# SquareSprite.net
KiCad netlist of a schematic drawn in EAGLE
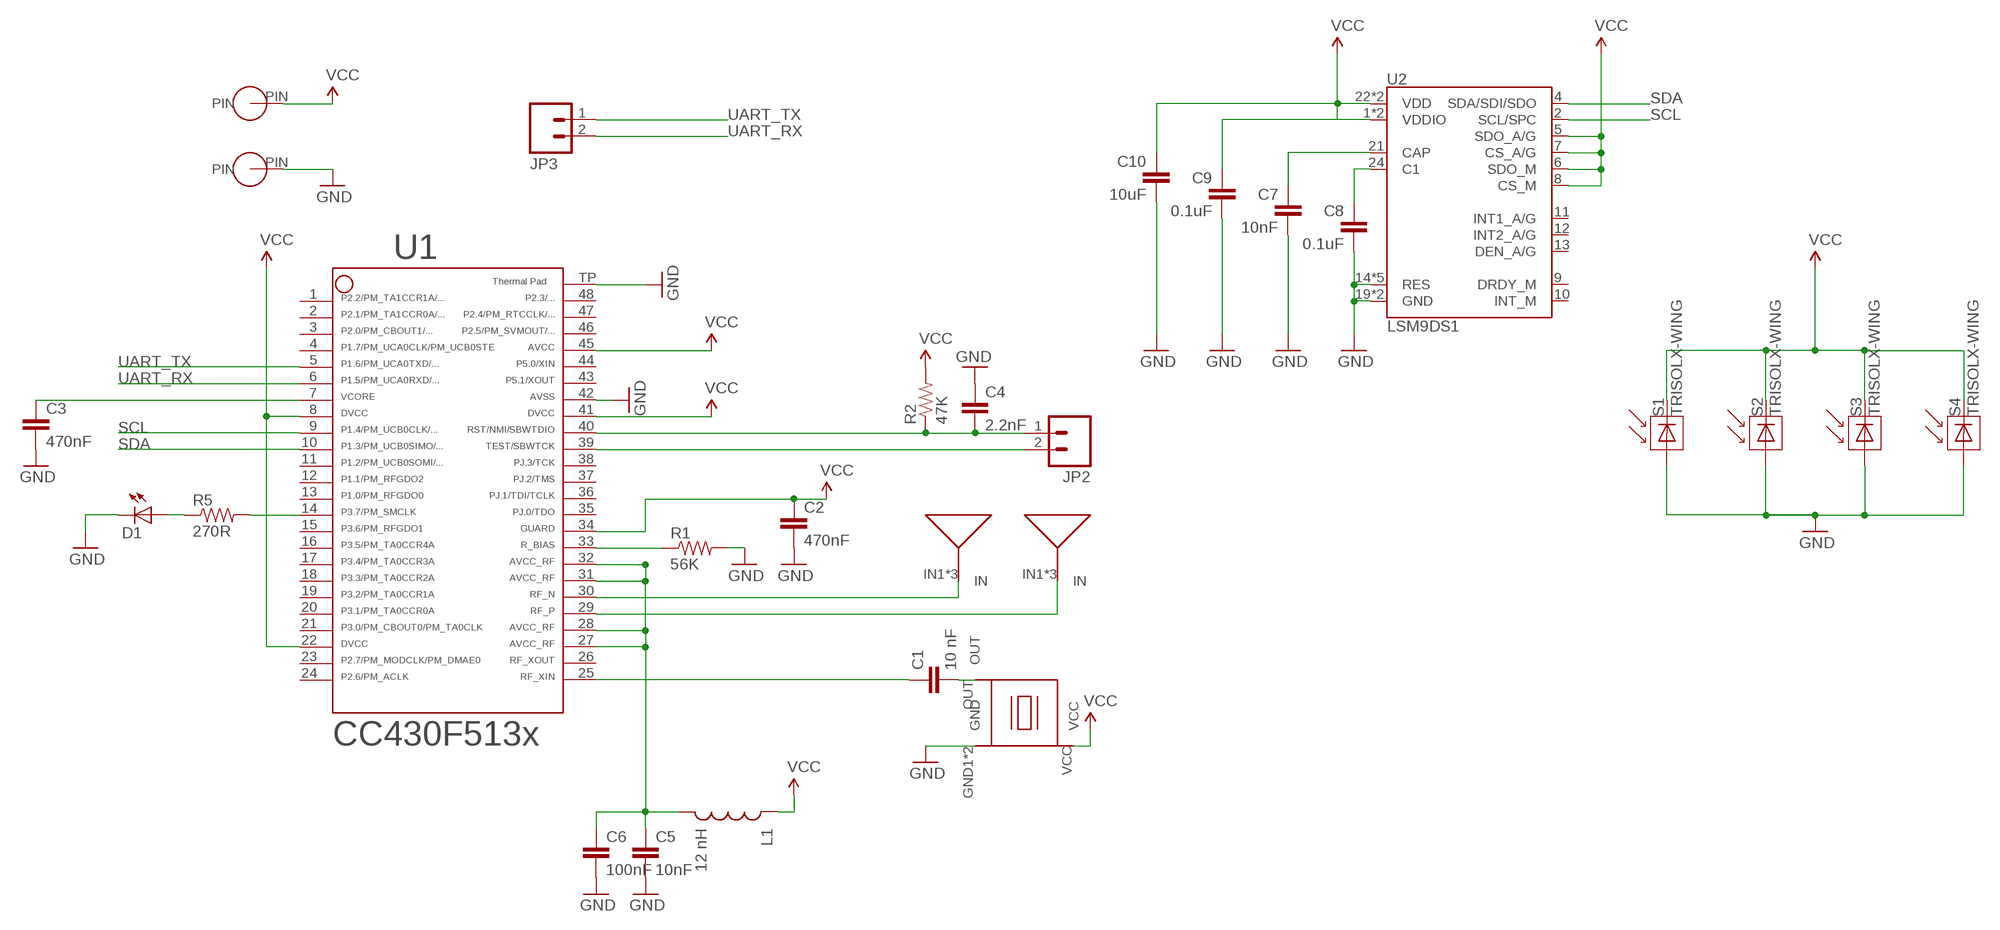
[diagram p0: schematic, sheet 1]

(export (version "E")
  (design (tool "Eeschema 10.0.6"))
  (components
    (comp (ref "ANT-N")
      (value "ANTENNA")
      (footprint "eagle-import:ANTENNA")
      (libsource (lib "eagle-import") (part "ANTENNA"))
    )
    (comp (ref "ANT-P")
      (value "ANTENNA")
      (footprint "eagle-import:ANTENNA")
      (libsource (lib "eagle-import") (part "ANTENNA"))
    )
    (comp (ref "C1")
      (value "10 nF")
      (footprint "eagle-import:0603-CAP")
      (libsource (lib "eagle-import") (part "CAP0603-CAP"))
    )
    (comp (ref "C2")
      (value "470nF")
      (footprint "eagle-import:0603-CAP")
      (libsource (lib "eagle-import") (part "CAP0603-CAP"))
    )
    (comp (ref "C3")
      (value "470nF")
      (footprint "eagle-import:0603-CAP")
      (libsource (lib "eagle-import") (part "CAP0603-CAP"))
    )
    (comp (ref "C4")
      (value "2.2nF")
      (footprint "eagle-import:0603-CAP")
      (libsource (lib "eagle-import") (part "CAP0603-CAP"))
    )
    (comp (ref "C5")
      (value "10nF")
      (footprint "eagle-import:0603-CAP")
      (libsource (lib "eagle-import") (part "CAP0603-CAP"))
    )
    (comp (ref "C6")
      (value "100nF")
      (footprint "eagle-import:0603-CAP")
      (libsource (lib "eagle-import") (part "CAP0603-CAP"))
    )
    (comp (ref "C7")
      (value "10nF")
      (footprint "eagle-import:0603-CAP")
      (libsource (lib "eagle-import") (part "CAP0603-CAP"))
    )
    (comp (ref "C8")
      (value "0.1uF")
      (footprint "eagle-import:0603-CAP")
      (libsource (lib "eagle-import") (part "CAP0603-CAP"))
    )
    (comp (ref "C9")
      (value "0.1uF")
      (footprint "eagle-import:0603-CAP")
      (libsource (lib "eagle-import") (part "CAP0603-CAP"))
    )
    (comp (ref "C10")
      (value "10uF")
      (footprint "eagle-import:0603-CAP")
      (libsource (lib "eagle-import") (part "CAP0603-CAP"))
    )
    (comp (ref "D1")
      (value "LED0603")
      (footprint "eagle-import:LED-0603")
      (libsource (lib "eagle-import") (part "LED0603"))
    )
    (comp (ref "JP2")
      (value "M02PTH")
      (footprint "eagle-import:1X02")
      (libsource (lib "eagle-import") (part "M02PTH"))
    )
    (comp (ref "JP3")
      (value "M02PTH")
      (footprint "eagle-import:1X02")
      (libsource (lib "eagle-import") (part "M02PTH"))
    )
    (comp (ref "L1")
      (value "12 nH")
      (footprint "eagle-import:0603")
      (libsource (lib "eagle-import") (part "INDUCTOR0603"))
    )
    (comp (ref "P1")
      (value "SPRITE_PIN")
      (footprint "eagle-import:SPRITE_PIN")
      (libsource (lib "eagle-import") (part "SPRITE_PIN"))
    )
    (comp (ref "P2")
      (value "SPRITE_PIN")
      (footprint "eagle-import:SPRITE_PIN")
      (libsource (lib "eagle-import") (part "SPRITE_PIN"))
    )
    (comp (ref "R1")
      (value "56K")
      (footprint "eagle-import:0603-RES")
      (libsource (lib "eagle-import") (part "RESISTOR0603-RES"))
    )
    (comp (ref "R2")
      (value "47K")
      (footprint "eagle-import:0603-RES")
      (libsource (lib "eagle-import") (part "RESISTOR0603-RES"))
    )
    (comp (ref "R5")
      (value "270R")
      (footprint "eagle-import:0603-RES")
      (libsource (lib "eagle-import") (part "RESISTOR0603-RES"))
    )
    (comp (ref "S1")
      (value "TRISOLX-WING")
      (footprint "eagle-import:TRISOLX-T01")
      (libsource (lib "eagle-import") (part "TRISOLX-WING"))
    )
    (comp (ref "S2")
      (value "TRISOLX-WING")
      (footprint "eagle-import:TRISOLX-T01")
      (libsource (lib "eagle-import") (part "TRISOLX-WING"))
    )
    (comp (ref "S3")
      (value "TRISOLX-WING")
      (footprint "eagle-import:TRISOLX-T01")
      (libsource (lib "eagle-import") (part "TRISOLX-WING"))
    )
    (comp (ref "S4")
      (value "TRISOLX-WING")
      (footprint "eagle-import:TRISOLX-T01")
      (libsource (lib "eagle-import") (part "TRISOLX-WING"))
    )
    (comp (ref "U1")
      (value "CC430F5137")
      (footprint "eagle-import:RGZ48")
      (libsource (lib "eagle-import") (part "CC430F513X---RGZ48"))
    )
    (comp (ref "U2")
      (value "LSM9DS1")
      (footprint "eagle-import:LGA24-8X4")
      (libsource (lib "eagle-import") (part "LSM9DS1"))
    )
    (comp (ref "X1")
      (value "TCXO_7Z")
      (footprint "eagle-import:TXC_7Z")
      (libsource (lib "eagle-import") (part "TCXO_7Z"))
    )
  )
  (nets
    (net (code "1") (name "GND") (class "Default")
      (node (ref "C10") (pin "2") (pinfunction "2_2") (pintype "passive"))
      (node (ref "C2") (pin "2") (pinfunction "2_2") (pintype "passive"))
      (node (ref "C3") (pin "2") (pinfunction "2_2") (pintype "passive"))
      (node (ref "C4") (pin "1") (pinfunction "1_1") (pintype "passive"))
      (node (ref "C5") (pin "2") (pinfunction "2_2") (pintype "passive"))
      (node (ref "C6") (pin "2") (pinfunction "2_2") (pintype "passive"))
      (node (ref "C7") (pin "2") (pinfunction "2_2") (pintype "passive"))
      (node (ref "C8") (pin "2") (pinfunction "2_2") (pintype "passive"))
      (node (ref "C9") (pin "2") (pinfunction "2_2") (pintype "passive"))
      (node (ref "D1") (pin "C") (pinfunction "C_C") (pintype "passive"))
      (node (ref "P1") (pin "PIN") (pinfunction "PIN_PIN") (pintype "bidirectional"))
      (node (ref "R1") (pin "2") (pinfunction "2_2") (pintype "passive"))
      (node (ref "S1") (pin "P$3") (pinfunction "A_P$3") (pintype "passive"))
      (node (ref "S2") (pin "P$3") (pinfunction "A_P$3") (pintype "passive"))
      (node (ref "S3") (pin "P$3") (pinfunction "A_P$3") (pintype "passive"))
      (node (ref "S4") (pin "P$3") (pinfunction "A_P$3") (pintype "passive"))
      (node (ref "U1") (pin "42") (pinfunction "42_42") (pintype "power_in"))
      (node (ref "U1") (pin "TP") (pinfunction "49_TP") (pintype "power_in"))
      (node (ref "U2") (pin "14") (pinfunction "RES_14") (pintype "bidirectional"))
      (node (ref "U2") (pin "15") (pinfunction "RES_15") (pintype "bidirectional"))
      (node (ref "U2") (pin "16") (pinfunction "RES_16") (pintype "bidirectional"))
      (node (ref "U2") (pin "17") (pinfunction "RES_17") (pintype "bidirectional"))
      (node (ref "U2") (pin "18") (pinfunction "RES_18") (pintype "bidirectional"))
      (node (ref "U2") (pin "19") (pinfunction "GND_19") (pintype "bidirectional"))
      (node (ref "U2") (pin "20") (pinfunction "GND_20") (pintype "bidirectional"))
      (node (ref "X1") (pin "GND1") (pinfunction "GND_GND1") (pintype "bidirectional"))
      (node (ref "X1") (pin "GND2") (pinfunction "GND_GND2") (pintype "bidirectional"))
    )
    (net (code "2") (name "Net-(ANT-N-IN-PadIN1)") (class "Default")
      (node (ref "ANT-N") (pin "IN1") (pinfunction "IN_IN1") (pintype "bidirectional"))
      (node (ref "ANT-N") (pin "IN2") (pinfunction "IN_IN2") (pintype "bidirectional"))
      (node (ref "ANT-N") (pin "IN3") (pinfunction "IN_IN3") (pintype "bidirectional"))
      (node (ref "U1") (pin "30") (pinfunction "30_30") (pintype "bidirectional"))
    )
    (net (code "3") (name "Net-(ANT-P-IN-PadIN1)") (class "Default")
      (node (ref "ANT-P") (pin "IN1") (pinfunction "IN_IN1") (pintype "bidirectional"))
      (node (ref "ANT-P") (pin "IN2") (pinfunction "IN_IN2") (pintype "bidirectional"))
      (node (ref "ANT-P") (pin "IN3") (pinfunction "IN_IN3") (pintype "bidirectional"))
      (node (ref "U1") (pin "29") (pinfunction "29_29") (pintype "bidirectional"))
    )
    (net (code "4") (name "Net-(C1-Pad1)") (class "Default")
      (node (ref "C1") (pin "1") (pinfunction "1_1") (pintype "passive"))
      (node (ref "U1") (pin "25") (pinfunction "25_25") (pintype "input"))
    )
    (net (code "5") (name "Net-(C1-Pad2)") (class "Default")
      (node (ref "C1") (pin "2") (pinfunction "2_2") (pintype "passive"))
      (node (ref "X1") (pin "OUT") (pinfunction "OUT_OUT") (pintype "bidirectional"))
    )
    (net (code "6") (name "Net-(C3-Pad1)") (class "Default")
      (node (ref "C3") (pin "1") (pinfunction "1_1") (pintype "passive"))
      (node (ref "U1") (pin "7") (pinfunction "7_7") (pintype "power_in"))
    )
    (net (code "7") (name "Net-(C4-Pad2)") (class "Default")
      (node (ref "C4") (pin "2") (pinfunction "2_2") (pintype "passive"))
      (node (ref "JP2") (pin "1") (pinfunction "1_1") (pintype "passive"))
      (node (ref "R2") (pin "1") (pinfunction "1_1") (pintype "passive"))
      (node (ref "U1") (pin "40") (pinfunction "40_40") (pintype "bidirectional"))
    )
    (net (code "8") (name "Net-(C5-Pad1)") (class "Default")
      (node (ref "C5") (pin "1") (pinfunction "1_1") (pintype "passive"))
      (node (ref "C6") (pin "1") (pinfunction "1_1") (pintype "passive"))
      (node (ref "L1") (pin "2") (pinfunction "2_2") (pintype "passive"))
      (node (ref "U1") (pin "27") (pinfunction "27_27") (pintype "power_in"))
      (node (ref "U1") (pin "28") (pinfunction "28_28") (pintype "bidirectional"))
      (node (ref "U1") (pin "31") (pinfunction "31_31") (pintype "power_in"))
      (node (ref "U1") (pin "32") (pinfunction "32_32") (pintype "power_in"))
    )
    (net (code "9") (name "Net-(D1-PadA)") (class "Default")
      (node (ref "D1") (pin "A") (pinfunction "A_A") (pintype "passive"))
      (node (ref "R5") (pin "1") (pinfunction "1_1") (pintype "passive"))
    )
    (net (code "10") (name "Net-(JP2-Pad2)") (class "Default")
      (node (ref "JP2") (pin "2") (pinfunction "2_2") (pintype "passive"))
      (node (ref "U1") (pin "39") (pinfunction "39_39") (pintype "input"))
    )
    (net (code "11") (name "Net-(R1-Pad1)") (class "Default")
      (node (ref "R1") (pin "1") (pinfunction "1_1") (pintype "passive"))
      (node (ref "U1") (pin "33") (pinfunction "33_33") (pintype "power_in"))
    )
    (net (code "12") (name "Net-(R5-Pad2)") (class "Default")
      (node (ref "R5") (pin "2") (pinfunction "2_2") (pintype "passive"))
      (node (ref "U1") (pin "14") (pinfunction "14_14") (pintype "bidirectional"))
    )
    (net (code "13") (name "Net-(U2-C1)") (class "Default")
      (node (ref "C8") (pin "1") (pinfunction "1_1") (pintype "passive"))
      (node (ref "U2") (pin "24") (pinfunction "C1_24") (pintype "bidirectional"))
    )
    (net (code "14") (name "Net-(U2-CAP)") (class "Default")
      (node (ref "C7") (pin "1") (pinfunction "1_1") (pintype "passive"))
      (node (ref "U2") (pin "21") (pinfunction "CAP_21") (pintype "bidirectional"))
    )
    (net (code "15") (name "SCL") (class "Default")
      (node (ref "U1") (pin "9") (pinfunction "9_9") (pintype "bidirectional"))
      (node (ref "U2") (pin "2") (pinfunction "SCL/SPC_2") (pintype "bidirectional"))
    )
    (net (code "16") (name "SDA") (class "Default")
      (node (ref "U1") (pin "10") (pinfunction "10_10") (pintype "bidirectional"))
      (node (ref "U2") (pin "4") (pinfunction "SDA/SDI/SDO_4") (pintype "bidirectional"))
    )
    (net (code "17") (name "UART_RX") (class "Default")
      (node (ref "JP3") (pin "2") (pinfunction "2_2") (pintype "passive"))
      (node (ref "U1") (pin "6") (pinfunction "6_6") (pintype "bidirectional"))
    )
    (net (code "18") (name "UART_TX") (class "Default")
      (node (ref "JP3") (pin "1") (pinfunction "1_1") (pintype "passive"))
      (node (ref "U1") (pin "5") (pinfunction "5_5") (pintype "bidirectional"))
    )
    (net (code "19") (name "VCC") (class "Default")
      (node (ref "C10") (pin "1") (pinfunction "1_1") (pintype "passive"))
      (node (ref "C2") (pin "1") (pinfunction "1_1") (pintype "passive"))
      (node (ref "C9") (pin "1") (pinfunction "1_1") (pintype "passive"))
      (node (ref "L1") (pin "1") (pinfunction "1_1") (pintype "passive"))
      (node (ref "P2") (pin "PIN") (pinfunction "PIN_PIN") (pintype "bidirectional"))
      (node (ref "R2") (pin "2") (pinfunction "2_2") (pintype "passive"))
      (node (ref "S1") (pin "P$2") (pinfunction "C_P$2") (pintype "passive"))
      (node (ref "S2") (pin "P$2") (pinfunction "C_P$2") (pintype "passive"))
      (node (ref "S3") (pin "P$2") (pinfunction "C_P$2") (pintype "passive"))
      (node (ref "S4") (pin "P$2") (pinfunction "C_P$2") (pintype "passive"))
      (node (ref "U1") (pin "22") (pinfunction "22_22") (pintype "power_in"))
      (node (ref "U1") (pin "34") (pinfunction "34_34") (pintype "power_in"))
      (node (ref "U1") (pin "41") (pinfunction "41_41") (pintype "power_in"))
      (node (ref "U1") (pin "45") (pinfunction "45_45") (pintype "input"))
      (node (ref "U1") (pin "8") (pinfunction "8_8") (pintype "power_in"))
      (node (ref "U2") (pin "1") (pinfunction "VDDIO_1") (pintype "bidirectional"))
      (node (ref "U2") (pin "22") (pinfunction "VDD_22") (pintype "bidirectional"))
      (node (ref "U2") (pin "23") (pinfunction "VDD_23") (pintype "bidirectional"))
      (node (ref "U2") (pin "3") (pinfunction "VDDIO_3") (pintype "bidirectional"))
      (node (ref "U2") (pin "5") (pinfunction "SDO_A/G_5") (pintype "bidirectional"))
      (node (ref "U2") (pin "6") (pinfunction "SDO_M_6") (pintype "bidirectional"))
      (node (ref "U2") (pin "7") (pinfunction "CS_A/G_7") (pintype "bidirectional"))
      (node (ref "U2") (pin "8") (pinfunction "CS_M_8") (pintype "bidirectional"))
      (node (ref "X1") (pin "VCC") (pinfunction "VCC_VCC") (pintype "bidirectional"))
    )
    (net (code "20") (name "unconnected-(U1-Pad1)") (class "Default")
      (node (ref "U1") (pin "1") (pinfunction "1_1") (pintype "bidirectional"))
    )
    (net (code "21") (name "unconnected-(U1-Pad2)") (class "Default")
      (node (ref "U1") (pin "2") (pinfunction "2_2") (pintype "bidirectional"))
    )
    (net (code "22") (name "unconnected-(U1-Pad3)") (class "Default")
      (node (ref "U1") (pin "3") (pinfunction "3_3") (pintype "bidirectional"))
    )
    (net (code "23") (name "unconnected-(U1-Pad4)") (class "Default")
      (node (ref "U1") (pin "4") (pinfunction "4_4") (pintype "bidirectional"))
    )
    (net (code "24") (name "unconnected-(U1-Pad11)") (class "Default")
      (node (ref "U1") (pin "11") (pinfunction "11_11") (pintype "bidirectional"))
    )
    (net (code "25") (name "unconnected-(U1-Pad12)") (class "Default")
      (node (ref "U1") (pin "12") (pinfunction "12_12") (pintype "bidirectional"))
    )
    (net (code "26") (name "unconnected-(U1-Pad13)") (class "Default")
      (node (ref "U1") (pin "13") (pinfunction "13_13") (pintype "bidirectional"))
    )
    (net (code "27") (name "unconnected-(U1-Pad15)") (class "Default")
      (node (ref "U1") (pin "15") (pinfunction "15_15") (pintype "bidirectional"))
    )
    (net (code "28") (name "unconnected-(U1-Pad16)") (class "Default")
      (node (ref "U1") (pin "16") (pinfunction "16_16") (pintype "bidirectional"))
    )
    (net (code "29") (name "unconnected-(U1-Pad17)") (class "Default")
      (node (ref "U1") (pin "17") (pinfunction "17_17") (pintype "bidirectional"))
    )
    (net (code "30") (name "unconnected-(U1-Pad18)") (class "Default")
      (node (ref "U1") (pin "18") (pinfunction "18_18") (pintype "bidirectional"))
    )
    (net (code "31") (name "unconnected-(U1-Pad19)") (class "Default")
      (node (ref "U1") (pin "19") (pinfunction "19_19") (pintype "bidirectional"))
    )
    (net (code "32") (name "unconnected-(U1-Pad20)") (class "Default")
      (node (ref "U1") (pin "20") (pinfunction "20_20") (pintype "bidirectional"))
    )
    (net (code "33") (name "unconnected-(U1-Pad21)") (class "Default")
      (node (ref "U1") (pin "21") (pinfunction "21_21") (pintype "bidirectional"))
    )
    (net (code "34") (name "unconnected-(U1-Pad23)") (class "Default")
      (node (ref "U1") (pin "23") (pinfunction "23_23") (pintype "bidirectional"))
    )
    (net (code "35") (name "unconnected-(U1-Pad24)") (class "Default")
      (node (ref "U1") (pin "24") (pinfunction "24_24") (pintype "bidirectional"))
    )
    (net (code "36") (name "unconnected-(U1-Pad26)") (class "Default")
      (node (ref "U1") (pin "26") (pinfunction "26_26") (pintype "output"))
    )
    (net (code "37") (name "unconnected-(U1-Pad35)") (class "Default")
      (node (ref "U1") (pin "35") (pinfunction "35_35") (pintype "bidirectional"))
    )
    (net (code "38") (name "unconnected-(U1-Pad36)") (class "Default")
      (node (ref "U1") (pin "36") (pinfunction "36_36") (pintype "bidirectional"))
    )
    (net (code "39") (name "unconnected-(U1-Pad37)") (class "Default")
      (node (ref "U1") (pin "37") (pinfunction "37_37") (pintype "bidirectional"))
    )
    (net (code "40") (name "unconnected-(U1-Pad38)") (class "Default")
      (node (ref "U1") (pin "38") (pinfunction "38_38") (pintype "bidirectional"))
    )
    (net (code "41") (name "unconnected-(U1-Pad43)") (class "Default")
      (node (ref "U1") (pin "43") (pinfunction "43_43") (pintype "input"))
    )
    (net (code "42") (name "unconnected-(U1-Pad44)") (class "Default")
      (node (ref "U1") (pin "44") (pinfunction "44_44") (pintype "input"))
    )
    (net (code "43") (name "unconnected-(U1-Pad46)") (class "Default")
      (node (ref "U1") (pin "46") (pinfunction "46_46") (pintype "bidirectional"))
    )
    (net (code "44") (name "unconnected-(U1-Pad47)") (class "Default")
      (node (ref "U1") (pin "47") (pinfunction "47_47") (pintype "input"))
    )
    (net (code "45") (name "unconnected-(U1-Pad48)") (class "Default")
      (node (ref "U1") (pin "48") (pinfunction "48_48") (pintype "bidirectional"))
    )
    (net (code "46") (name "unconnected-(U2-DEN_A{slash}G-Pad13)") (class "Default")
      (node (ref "U2") (pin "13") (pinfunction "DEN_A/G_13") (pintype "bidirectional"))
    )
    (net (code "47") (name "unconnected-(U2-DRDY_M-Pad9)") (class "Default")
      (node (ref "U2") (pin "9") (pinfunction "DRDY_M_9") (pintype "bidirectional"))
    )
    (net (code "48") (name "unconnected-(U2-INT1_A{slash}G-Pad11)") (class "Default")
      (node (ref "U2") (pin "11") (pinfunction "INT1_A/G_11") (pintype "bidirectional"))
    )
    (net (code "49") (name "unconnected-(U2-INT2_A{slash}G-Pad12)") (class "Default")
      (node (ref "U2") (pin "12") (pinfunction "INT2_A/G_12") (pintype "bidirectional"))
    )
    (net (code "50") (name "unconnected-(U2-INT_M-Pad10)") (class "Default")
      (node (ref "U2") (pin "10") (pinfunction "INT_M_10") (pintype "bidirectional"))
    )
  )
)
